# CH585D-DG-R0.net
KiCad netlist of a schematic drawn in Altium Designer
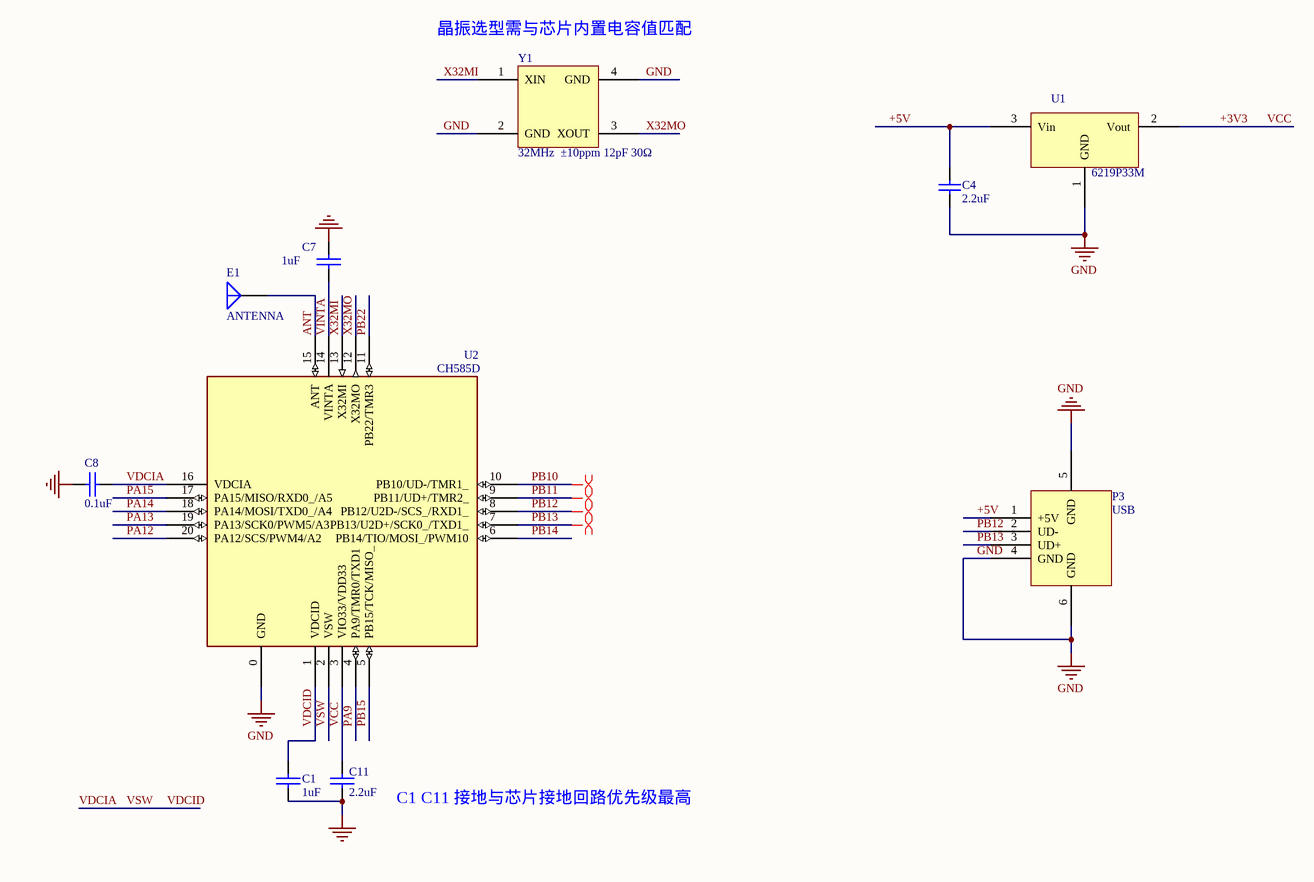
[diagram p0: CH585D-DG-R0.SchDoc]

(export (version "E")
  (design (tool "Eeschema 10.0.6"))
  (components
    (comp (ref "C1")
      (value "1uF")
      (footprint "0402_C")
      (description "Capacitor")
      (libsource (lib "*") (part "CAP"))
    )
    (comp (ref "C4")
      (value "2.2uF")
      (footprint "0402_C")
      (description "Capacitor")
      (fields (field (name "PUBLISHER") "Altium Limited"))
      (libsource (lib "Miscellaneous Devices") (part "Cap"))
    )
    (comp (ref "C7")
      (value "1uF")
      (footprint "0402_C")
      (description "Capacitor")
      (libsource (lib "") (part "CAP_1"))
    )
    (comp (ref "C8")
      (value "0.1uF")
      (footprint "0402_C")
      (description "Capacitor")
      (libsource (lib "") (part "CAP_1"))
    )
    (comp (ref "C11")
      (value "2.2uF")
      (footprint "0402_C")
      (description "Capacitor")
      (libsource (lib "") (part "CAP_1"))
    )
    (comp (ref "E1")
      (value "ANTENNA")
      (footprint "ANT-F-1-2.4G-0.8mmFR4")
      (description "Generic Antenna")
      (libsource (lib "*") (part "ANTENNA"))
    )
    (comp (ref "P3") (value "USB") (footprint "USBAM-4P") (libsource (lib "Schlib1") (part "USB")))
    (comp (ref "U1")
      (value "6219P33M")
      (footprint "SOT-23")
      (libsource (lib "wch_sch_others") (part "6219P33M"))
    )
    (comp (ref "U2")
      (value "CH585D")
      (footprint "QFN20_3X3")
      (description "RISC-V MCU with BLE/HSUSB/USB/ADC/PWM/SPI/2*UART")
      (libsource (lib "DHXXXSCH") (part "CH585D"))
    )
    (comp (ref "Y1")
      (value "32MHz  ±10ppm 12pF 30Ω")
      (footprint "XT2016")
      (libsource (lib "wch_sch_others") (part "晶体"))
    )
  )
  (nets
    (net (code "1") (name "/+3V3") (class "Default")
      (node (ref "C11") (pin "2") (pinfunction "2_2") (pintype "passive"))
      (node (ref "U1") (pin "2") (pinfunction "Vout_2") (pintype "passive"))
      (node (ref "U2") (pin "3") (pinfunction "VIO33/VDD33_3") (pintype "power_in"))
    )
    (net (code "2") (name "/+5V") (class "Default")
      (node (ref "C4") (pin "2") (pinfunction "2_2") (pintype "passive"))
      (node (ref "P3") (pin "1") (pinfunction "+5V_1") (pintype "passive"))
      (node (ref "U1") (pin "3") (pinfunction "Vin_3") (pintype "passive"))
    )
    (net (code "3") (name "/ANT") (class "Default")
      (node (ref "E1") (pin "1") (pinfunction "A_1") (pintype "passive"))
      (node (ref "U2") (pin "15") (pinfunction "ANT_15") (pintype "bidirectional"))
    )
    (net (code "4") (name "/PA9") (class "Default")
      (node (ref "U2") (pin "4") (pinfunction "PA9/TMR0/TXD1_4") (pintype "bidirectional"))
    )
    (net (code "5") (name "/PA12") (class "Default")
      (node (ref "U2") (pin "20") (pinfunction "PA12/SCS/PWM4/A2_20") (pintype "bidirectional"))
    )
    (net (code "6") (name "/PA13") (class "Default")
      (node (ref "U2") (pin "19") (pinfunction "PA13/SCK0/PWM5/A3_19") (pintype "bidirectional"))
    )
    (net (code "7") (name "/PA14") (class "Default")
      (node (ref "U2") (pin "18") (pinfunction "PA14/MOSI/TXD0_/A4_18") (pintype "bidirectional"))
    )
    (net (code "8") (name "/PA15") (class "Default")
      (node (ref "U2") (pin "17") (pinfunction "PA15/MISO/RXD0_/A5_17") (pintype "bidirectional"))
    )
    (net (code "9") (name "/PB10") (class "Default")
      (node (ref "U2") (pin "10") (pinfunction "PB10/UD-/TMR1__10") (pintype "bidirectional"))
    )
    (net (code "10") (name "/PB11") (class "Default")
      (node (ref "U2") (pin "9") (pinfunction "PB11/UD+/TMR2__9") (pintype "bidirectional"))
    )
    (net (code "11") (name "/PB12") (class "Default")
      (node (ref "P3") (pin "2") (pinfunction "UD-_2") (pintype "passive"))
      (node (ref "U2") (pin "8") (pinfunction "PB12/U2D-/SCS_/RXD1__8") (pintype "bidirectional"))
    )
    (net (code "12") (name "/PB13") (class "Default")
      (node (ref "P3") (pin "3") (pinfunction "UD+_3") (pintype "passive"))
      (node (ref "U2") (pin "7") (pinfunction "PB13/U2D+/SCK0_/TXD1__7") (pintype "bidirectional"))
    )
    (net (code "13") (name "/PB14") (class "Default")
      (node (ref "U2") (pin "6") (pinfunction "PB14/TIO/MOSI_/PWM10_6") (pintype "bidirectional"))
    )
    (net (code "14") (name "/PB15") (class "Default")
      (node (ref "U2") (pin "5") (pinfunction "PB15/TCK/MISO__5") (pintype "bidirectional"))
    )
    (net (code "15") (name "/PB22") (class "Default")
      (node (ref "U2") (pin "11") (pinfunction "PB22/TMR3_11") (pintype "bidirectional"))
    )
    (net (code "16") (name "/VDCIA") (class "Default")
      (node (ref "C1") (pin "2") (pinfunction "2_2") (pintype "passive"))
      (node (ref "C8") (pin "1") (pinfunction "1_1") (pintype "passive"))
      (node (ref "U2") (pin "1") (pinfunction "VDCID_1") (pintype "power_in"))
      (node (ref "U2") (pin "16") (pinfunction "VDCIA_16") (pintype "power_in"))
      (node (ref "U2") (pin "2") (pinfunction "VSW_2") (pintype "power_in"))
    )
    (net (code "17") (name "/VINTA") (class "Default")
      (node (ref "C7") (pin "1") (pinfunction "1_1") (pintype "passive"))
      (node (ref "U2") (pin "14") (pinfunction "VINTA_14") (pintype "power_in"))
    )
    (net (code "18") (name "/X32MI") (class "Default")
      (node (ref "U2") (pin "13") (pinfunction "X32MI_13") (pintype "input"))
      (node (ref "Y1") (pin "1") (pinfunction "XIN_1") (pintype "passive"))
    )
    (net (code "19") (name "/X32MO") (class "Default")
      (node (ref "U2") (pin "12") (pinfunction "X32MO_12") (pintype "output"))
      (node (ref "Y1") (pin "3") (pinfunction "XOUT_3") (pintype "passive"))
    )
    (net (code "20") (name "GND") (class "Default")
      (node (ref "C1") (pin "1") (pinfunction "1_1") (pintype "passive"))
      (node (ref "C11") (pin "1") (pinfunction "1_1") (pintype "passive"))
      (node (ref "C4") (pin "1") (pinfunction "1_1") (pintype "passive"))
      (node (ref "C7") (pin "2") (pinfunction "2_2") (pintype "passive"))
      (node (ref "C8") (pin "2") (pinfunction "2_2") (pintype "passive"))
      (node (ref "P3") (pin "4") (pinfunction "GND_4") (pintype "passive"))
      (node (ref "P3") (pin "5") (pinfunction "GND_5") (pintype "passive"))
      (node (ref "P3") (pin "6") (pinfunction "GND_6") (pintype "passive"))
      (node (ref "U1") (pin "1") (pinfunction "GND_1") (pintype "passive"))
      (node (ref "U2") (pin "0") (pinfunction "GND_0") (pintype "power_in"))
      (node (ref "Y1") (pin "2") (pinfunction "GND_2") (pintype "passive"))
      (node (ref "Y1") (pin "4") (pinfunction "GND_4") (pintype "passive"))
    )
  )
)
